# main.net
KiCad netlist of a schematic drawn in Altium Designer
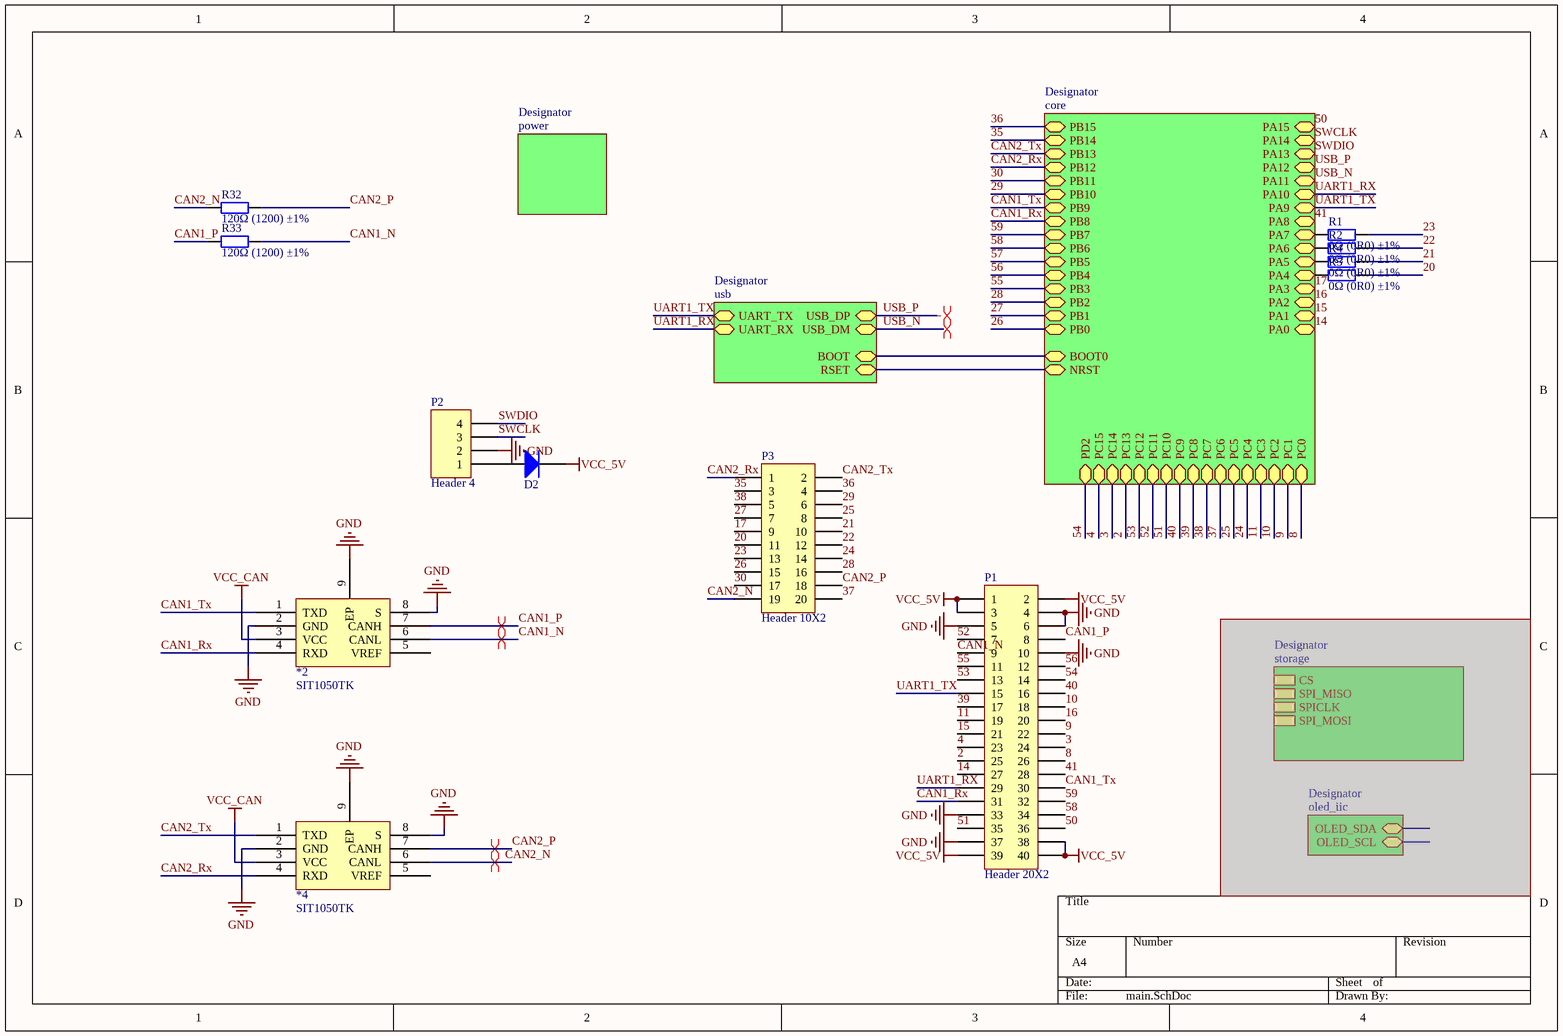
[diagram p0: main.SchDoc]

(export (version "E")
  (design (tool "Eeschema 10.0.6"))
  (components
    (comp (ref "*2")
      (value "SIT1050TK")
      (footprint "DFN3x3-8")
      (libsource (lib "ESP_SCH") (part "SIT1050TK"))
    )
    (comp (ref "*4")
      (value "SIT1050TK")
      (footprint "DFN3x3-8")
      (libsource (lib "ESP_SCH") (part "SIT1050TK"))
    )
    (comp (ref "D2")
      (value "二极管-5819W")
      (footprint "SOD-323")
      (description "40V")
      (libsource (lib "Planck-Pi-DK") (part "二极管-5819W"))
    )
    (comp (ref "P1")
      (value "Header 20X2")
      (footprint "HEADER_0.8mm_2x20P_G")
      (description "Header, 20-Pin, Dual row")
      (fields (field (name "PUBLISHER") "Altium Limited"))
      (libsource (lib "Miscellaneous Connectors") (part "Header 20X2"))
    )
    (comp (ref "P2")
      (value "Header 4")
      (footprint "HDR1X4")
      (description "Header, 4-Pin")
      (fields (field (name "PUBLISHER") "Altium Limited"))
      (libsource (lib "Miscellaneous Connectors") (part "Header 4"))
    )
    (comp (ref "P3")
      (value "Header 10X2")
      (footprint "HEAER_0.8mm_2x10P_M")
      (description "Header, 10-Pin, Dual row")
      (fields (field (name "PUBLISHER") "Altium Limited"))
      (libsource (lib "Miscellaneous Connectors") (part "Header 10X2"))
    )
    (comp (ref "R1")
      (value "0Ω (0R0) ±1%")
      (footprint "LC-0402_R")
      (description "贴片电阻")
      (libsource (lib "Miscellaneous Devices LC") (part "0402 0Ω (0R0) 1%"))
    )
    (comp (ref "R2")
      (value "0Ω (0R0) ±1%")
      (footprint "LC-0402_R")
      (description "贴片电阻")
      (libsource (lib "Miscellaneous Devices LC") (part "0402 0Ω (0R0) 1%"))
    )
    (comp (ref "R4")
      (value "0Ω (0R0) ±1%")
      (footprint "LC-0402_R")
      (description "贴片电阻")
      (libsource (lib "Miscellaneous Devices LC") (part "0402 0Ω (0R0) 1%"))
    )
    (comp (ref "R5")
      (value "0Ω (0R0) ±1%")
      (footprint "LC-0402_R")
      (description "贴片电阻")
      (libsource (lib "Miscellaneous Devices LC") (part "0402 0Ω (0R0) 1%"))
    )
    (comp (ref "R32")
      (value "120Ω (1200) ±1%")
      (footprint "LC-0402_R")
      (description "贴片电阻")
      (libsource (lib "Miscellaneous Devices LC") (part "0402 120Ω (1200) 1%"))
    )
    (comp (ref "R33")
      (value "120Ω (1200) ±1%")
      (footprint "LC-0402_R")
      (description "贴片电阻")
      (libsource (lib "Miscellaneous Devices LC") (part "0402 120Ω (1200) 1%"))
    )
  )
  (nets
    (net (code "1") (name "/2") (class "Default")
      (node (ref "P1") (pin "25") (pinfunction "25_25") (pintype "passive"))
    )
    (net (code "2") (name "/3") (class "Default")
      (node (ref "P1") (pin "24") (pinfunction "24_24") (pintype "passive"))
    )
    (net (code "3") (name "/4") (class "Default")
      (node (ref "P1") (pin "23") (pinfunction "23_23") (pintype "passive"))
    )
    (net (code "4") (name "/8") (class "Default")
      (node (ref "P1") (pin "26") (pinfunction "26_26") (pintype "passive"))
    )
    (net (code "5") (name "/9") (class "Default")
      (node (ref "P1") (pin "22") (pinfunction "22_22") (pintype "passive"))
    )
    (net (code "6") (name "/10") (class "Default")
      (node (ref "P1") (pin "18") (pinfunction "18_18") (pintype "passive"))
    )
    (net (code "7") (name "/11") (class "Default")
      (node (ref "P1") (pin "19") (pinfunction "19_19") (pintype "passive"))
    )
    (net (code "8") (name "/14") (class "Default")
      (node (ref "P1") (pin "27") (pinfunction "27_27") (pintype "passive"))
    )
    (net (code "9") (name "/15") (class "Default")
      (node (ref "P1") (pin "21") (pinfunction "21_21") (pintype "passive"))
    )
    (net (code "10") (name "/16") (class "Default")
      (node (ref "P1") (pin "20") (pinfunction "20_20") (pintype "passive"))
    )
    (net (code "11") (name "/17") (class "Default")
      (node (ref "P3") (pin "9") (pinfunction "9_9") (pintype "passive"))
    )
    (net (code "12") (name "/20") (class "Default")
      (node (ref "P3") (pin "11") (pinfunction "11_11") (pintype "passive"))
      (node (ref "R5") (pin "2") (pinfunction "2_2") (pintype "passive"))
    )
    (net (code "13") (name "/21") (class "Default")
      (node (ref "P3") (pin "10") (pinfunction "10_10") (pintype "passive"))
      (node (ref "R4") (pin "2") (pinfunction "2_2") (pintype "passive"))
    )
    (net (code "14") (name "/22") (class "Default")
      (node (ref "P3") (pin "12") (pinfunction "12_12") (pintype "passive"))
      (node (ref "R2") (pin "2") (pinfunction "2_2") (pintype "passive"))
    )
    (net (code "15") (name "/23") (class "Default")
      (node (ref "P3") (pin "13") (pinfunction "13_13") (pintype "passive"))
      (node (ref "R1") (pin "2") (pinfunction "2_2") (pintype "passive"))
    )
    (net (code "16") (name "/24") (class "Default")
      (node (ref "P3") (pin "14") (pinfunction "14_14") (pintype "passive"))
    )
    (net (code "17") (name "/25") (class "Default")
      (node (ref "P3") (pin "8") (pinfunction "8_8") (pintype "passive"))
    )
    (net (code "18") (name "/26") (class "Default")
      (node (ref "P3") (pin "15") (pinfunction "15_15") (pintype "passive"))
    )
    (net (code "19") (name "/27") (class "Default")
      (node (ref "P3") (pin "7") (pinfunction "7_7") (pintype "passive"))
    )
    (net (code "20") (name "/28") (class "Default")
      (node (ref "P3") (pin "16") (pinfunction "16_16") (pintype "passive"))
    )
    (net (code "21") (name "/29") (class "Default")
      (node (ref "P3") (pin "6") (pinfunction "6_6") (pintype "passive"))
    )
    (net (code "22") (name "/30") (class "Default")
      (node (ref "P3") (pin "17") (pinfunction "17_17") (pintype "passive"))
    )
    (net (code "23") (name "/35") (class "Default")
      (node (ref "P3") (pin "3") (pinfunction "3_3") (pintype "passive"))
    )
    (net (code "24") (name "/36") (class "Default")
      (node (ref "P3") (pin "4") (pinfunction "4_4") (pintype "passive"))
    )
    (net (code "25") (name "/37") (class "Default")
      (node (ref "P3") (pin "20") (pinfunction "20_20") (pintype "passive"))
    )
    (net (code "26") (name "/38") (class "Default")
      (node (ref "P3") (pin "5") (pinfunction "5_5") (pintype "passive"))
    )
    (net (code "27") (name "/39") (class "Default")
      (node (ref "P1") (pin "17") (pinfunction "17_17") (pintype "passive"))
    )
    (net (code "28") (name "/40") (class "Default")
      (node (ref "P1") (pin "16") (pinfunction "16_16") (pintype "passive"))
    )
    (net (code "29") (name "/41") (class "Default")
      (node (ref "P1") (pin "28") (pinfunction "28_28") (pintype "passive"))
    )
    (net (code "30") (name "/50") (class "Default")
      (node (ref "P1") (pin "36") (pinfunction "36_36") (pintype "passive"))
    )
    (net (code "31") (name "/51") (class "Default")
      (node (ref "P1") (pin "35") (pinfunction "35_35") (pintype "passive"))
    )
    (net (code "32") (name "/52") (class "Default")
      (node (ref "P1") (pin "7") (pinfunction "7_7") (pintype "passive"))
    )
    (net (code "33") (name "/53") (class "Default")
      (node (ref "P1") (pin "13") (pinfunction "13_13") (pintype "passive"))
    )
    (net (code "34") (name "/54") (class "Default")
      (node (ref "P1") (pin "14") (pinfunction "14_14") (pintype "passive"))
    )
    (net (code "35") (name "/55") (class "Default")
      (node (ref "P1") (pin "11") (pinfunction "11_11") (pintype "passive"))
    )
    (net (code "36") (name "/56") (class "Default")
      (node (ref "P1") (pin "12") (pinfunction "12_12") (pintype "passive"))
    )
    (net (code "38") (name "/58") (class "Default")
      (node (ref "P1") (pin "34") (pinfunction "34_34") (pintype "passive"))
    )
    (net (code "39") (name "/59") (class "Default")
      (node (ref "P1") (pin "32") (pinfunction "32_32") (pintype "passive"))
    )
    (net (code "41") (name "/CAN1_N") (class "Default")
      (node (ref "*2") (pin "6") (pinfunction "CANL_6") (pintype "passive"))
      (node (ref "P1") (pin "9") (pinfunction "9_9") (pintype "passive"))
      (node (ref "R33") (pin "2") (pinfunction "2_2") (pintype "passive"))
    )
    (net (code "42") (name "/CAN1_P") (class "Default")
      (node (ref "*2") (pin "7") (pinfunction "CANH_7") (pintype "passive"))
      (node (ref "P1") (pin "8") (pinfunction "8_8") (pintype "passive"))
      (node (ref "R33") (pin "1") (pinfunction "1_1") (pintype "passive"))
    )
    (net (code "43") (name "/CAN1_Rx") (class "Default")
      (node (ref "*2") (pin "4") (pinfunction "RXD_4") (pintype "passive"))
      (node (ref "P1") (pin "31") (pinfunction "31_31") (pintype "passive"))
    )
    (net (code "44") (name "/CAN1_Tx") (class "Default")
      (node (ref "*2") (pin "1") (pinfunction "TXD_1") (pintype "passive"))
      (node (ref "P1") (pin "30") (pinfunction "30_30") (pintype "passive"))
    )
    (net (code "45") (name "/CAN2_N") (class "Default")
      (node (ref "*4") (pin "6") (pinfunction "CANL_6") (pintype "passive"))
      (node (ref "P3") (pin "19") (pinfunction "19_19") (pintype "passive"))
      (node (ref "R32") (pin "1") (pinfunction "1_1") (pintype "passive"))
    )
    (net (code "46") (name "/CAN2_P") (class "Default")
      (node (ref "*4") (pin "7") (pinfunction "CANH_7") (pintype "passive"))
      (node (ref "P3") (pin "18") (pinfunction "18_18") (pintype "passive"))
      (node (ref "R32") (pin "2") (pinfunction "2_2") (pintype "passive"))
    )
    (net (code "47") (name "/CAN2_Rx") (class "Default")
      (node (ref "*4") (pin "4") (pinfunction "RXD_4") (pintype "passive"))
      (node (ref "P3") (pin "1") (pinfunction "1_1") (pintype "passive"))
    )
    (net (code "48") (name "/CAN2_Tx") (class "Default")
      (node (ref "*4") (pin "1") (pinfunction "TXD_1") (pintype "passive"))
      (node (ref "P3") (pin "2") (pinfunction "2_2") (pintype "passive"))
    )
    (net (code "53") (name "/PA4") (class "Default")
      (node (ref "R5") (pin "1") (pinfunction "1_1") (pintype "passive"))
    )
    (net (code "54") (name "/PA5") (class "Default")
      (node (ref "R4") (pin "1") (pinfunction "1_1") (pintype "passive"))
    )
    (net (code "55") (name "/PA6") (class "Default")
      (node (ref "R2") (pin "1") (pinfunction "1_1") (pintype "passive"))
    )
    (net (code "56") (name "/PA7") (class "Default")
      (node (ref "R1") (pin "1") (pinfunction "1_1") (pintype "passive"))
    )
    (net (code "60") (name "/SWCLK") (class "Default")
      (node (ref "P2") (pin "3") (pinfunction "3_3") (pintype "passive"))
    )
    (net (code "61") (name "/SWDIO") (class "Default")
      (node (ref "P2") (pin "4") (pinfunction "4_4") (pintype "passive"))
    )
    (net (code "62") (name "/UART1_RX") (class "Default")
      (node (ref "P1") (pin "29") (pinfunction "29_29") (pintype "passive"))
    )
    (net (code "63") (name "/UART1_TX") (class "Default")
      (node (ref "P1") (pin "15") (pinfunction "15_15") (pintype "passive"))
    )
    (net (code "66") (name "GND") (class "Default")
      (node (ref "*2") (pin "2") (pinfunction "GND_2") (pintype "passive"))
      (node (ref "*2") (pin "8") (pinfunction "S_8") (pintype "passive"))
      (node (ref "*2") (pin "9") (pinfunction "EP_9") (pintype "passive"))
      (node (ref "*4") (pin "2") (pinfunction "GND_2") (pintype "passive"))
      (node (ref "*4") (pin "8") (pinfunction "S_8") (pintype "passive"))
      (node (ref "*4") (pin "9") (pinfunction "EP_9") (pintype "passive"))
      (node (ref "P1") (pin "10") (pinfunction "10_10") (pintype "passive"))
      (node (ref "P1") (pin "33") (pinfunction "33_33") (pintype "passive"))
      (node (ref "P1") (pin "37") (pinfunction "37_37") (pintype "passive"))
      (node (ref "P1") (pin "4") (pinfunction "4_4") (pintype "passive"))
      (node (ref "P1") (pin "5") (pinfunction "5_5") (pintype "passive"))
      (node (ref "P1") (pin "6") (pinfunction "6_6") (pintype "passive"))
      (node (ref "P2") (pin "2") (pinfunction "2_2") (pintype "passive"))
    )
    (net (code "67") (name "Net-(D2-A)") (class "Default")
      (node (ref "D2") (pin "1") (pinfunction "A_1") (pintype "passive"))
      (node (ref "P2") (pin "1") (pinfunction "1_1") (pintype "passive"))
    )
    (net (code "68") (name "VCC_5V") (class "Default")
      (node (ref "D2") (pin "2") (pinfunction "K_2") (pintype "passive"))
      (node (ref "P1") (pin "1") (pinfunction "1_1") (pintype "passive"))
      (node (ref "P1") (pin "2") (pinfunction "2_2") (pintype "passive"))
      (node (ref "P1") (pin "3") (pinfunction "3_3") (pintype "passive"))
      (node (ref "P1") (pin "38") (pinfunction "38_38") (pintype "passive"))
      (node (ref "P1") (pin "39") (pinfunction "39_39") (pintype "passive"))
      (node (ref "P1") (pin "40") (pinfunction "40_40") (pintype "passive"))
    )
    (net (code "69") (name "VCC_CAN") (class "Default")
      (node (ref "*2") (pin "3") (pinfunction "VCC_3") (pintype "passive"))
      (node (ref "*4") (pin "3") (pinfunction "VCC_3") (pintype "passive"))
    )
    (net (code "70") (name "unconnected-(*2-VREF-Pad5)") (class "Default")
      (node (ref "*2") (pin "5") (pinfunction "VREF_5") (pintype "passive"))
    )
    (net (code "71") (name "unconnected-(*4-VREF-Pad5)") (class "Default")
      (node (ref "*4") (pin "5") (pinfunction "VREF_5") (pintype "passive"))
    )
  )
)
